# automotive-mirror-microcontroller-net-la.net
KiCad netlist of a schematic drawn in Altium Designer
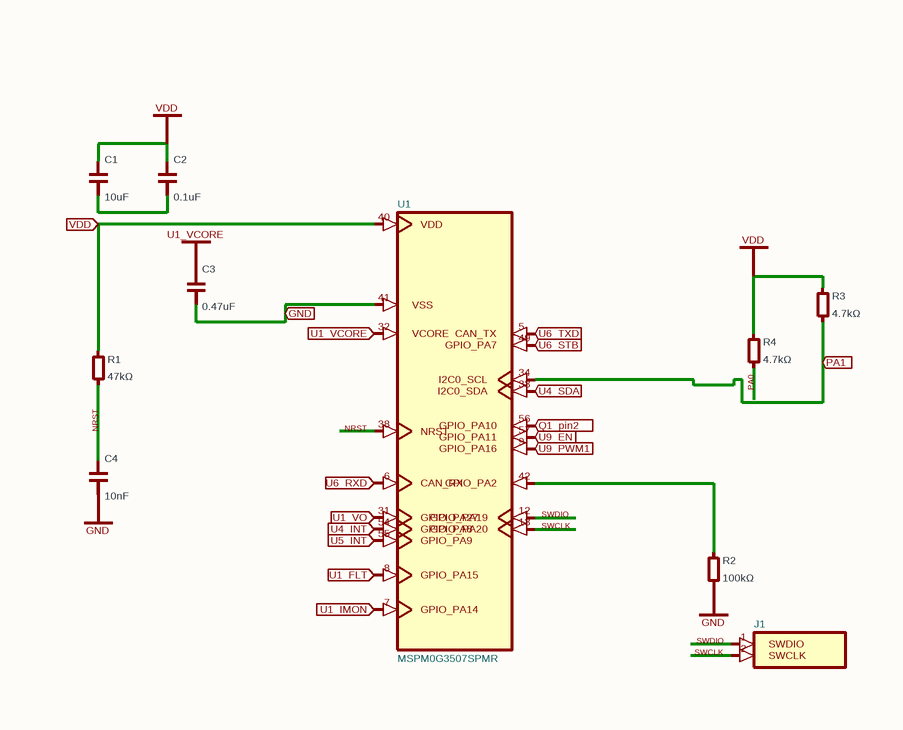
[diagram p0: automotive-mirror-microcontroller-net-label-text-4pt.SchDoc]

(export (version "E")
  (design (tool "Eeschema 10.0.6"))
  (components
    (comp (ref "C1") (value "10uF") (libsource (lib "altium-import") (part "root_0_capacitor_down_")))
    (comp (ref "C2") (value "0.1uF") (libsource (lib "altium-import") (part "root_0_capacitor_down_")))
    (comp (ref "C3") (value "0.47uF") (libsource (lib "altium-import") (part "root_0_capacitor_down_")))
    (comp (ref "C4") (value "10nF") (libsource (lib "altium-import") (part "root_0_capacitor_down_")))
    (comp (ref "J1") (value "~") (libsource (lib "altium-import") (part "root_0_J1_")))
    (comp (ref "R1") (value "47kΩ") (libsource (lib "altium-import") (part "root_0_boxresistor_up_")))
    (comp (ref "R2") (value "100kΩ") (libsource (lib "altium-import") (part "root_0_boxresistor_down_")))
    (comp (ref "R3") (value "4.7kΩ") (libsource (lib "altium-import") (part "root_0_boxresistor_up_")))
    (comp (ref "R4") (value "4.7kΩ") (libsource (lib "altium-import") (part "root_0_boxresistor_up_")))
    (comp (ref "U1") (value "~") (libsource (lib "altium-import") (part "root_0_U1_")))
  )
  (nets
    (net (code "1") (name "/PA1") (class "Default")
      (node (ref "R3") (pin "1") (pinfunction "anode_1") (pintype "input"))
      (node (ref "U1") (pin "34") (pinfunction "I2C0_SCL_34") (pintype "input"))
    )
    (net (code "2") (name "/Q1_pin2") (class "Default")
      (node (ref "U1") (pin "56") (pinfunction "GPIO_PA10_56") (pintype "input"))
    )
    (net (code "3") (name "/U1_FLT") (class "Default")
      (node (ref "U1") (pin "8") (pinfunction "GPIO_PA15_8") (pintype "input"))
    )
    (net (code "4") (name "/U1_IMON") (class "Default")
      (node (ref "U1") (pin "7") (pinfunction "GPIO_PA14_7") (pintype "input"))
    )
    (net (code "5") (name "/U1_VO") (class "Default")
      (node (ref "U1") (pin "31") (pinfunction "GPIO_PA27_31") (pintype "input"))
    )
    (net (code "6") (name "/U4_INT") (class "Default")
      (node (ref "U1") (pin "54") (pinfunction "GPIO_PA8_54") (pintype "input"))
    )
    (net (code "7") (name "/U4_SDA") (class "Default")
      (node (ref "U1") (pin "33") (pinfunction "I2C0_SDA_33") (pintype "input"))
    )
    (net (code "8") (name "/U5_INT") (class "Default")
      (node (ref "U1") (pin "55") (pinfunction "GPIO_PA9_55") (pintype "input"))
    )
    (net (code "9") (name "/U6_RXD") (class "Default")
      (node (ref "U1") (pin "6") (pinfunction "CAN_RX_6") (pintype "input"))
    )
    (net (code "10") (name "/U6_STB") (class "Default")
      (node (ref "U1") (pin "49") (pinfunction "GPIO_PA7_49") (pintype "input"))
    )
    (net (code "11") (name "/U6_TXD") (class "Default")
      (node (ref "U1") (pin "5") (pinfunction "CAN_TX_5") (pintype "input"))
    )
    (net (code "12") (name "/U9_EN") (class "Default")
      (node (ref "U1") (pin "57") (pinfunction "GPIO_PA11_57") (pintype "input"))
    )
    (net (code "13") (name "/U9_PWM1") (class "Default")
      (node (ref "U1") (pin "9") (pinfunction "GPIO_PA16_9") (pintype "input"))
    )
    (net (code "14") (name "GND") (class "Default")
      (node (ref "C3") (pin "2") (pinfunction "cathode_2") (pintype "input"))
      (node (ref "C4") (pin "2") (pinfunction "cathode_2") (pintype "input"))
      (node (ref "R2") (pin "2") (pinfunction "cathode_2") (pintype "input"))
      (node (ref "U1") (pin "41") (pinfunction "VSS_41") (pintype "input"))
    )
    (net (code "15") (name "Net-(C1-cathode)") (class "Default")
      (node (ref "C1") (pin "2") (pinfunction "cathode_2") (pintype "input"))
      (node (ref "C2") (pin "2") (pinfunction "cathode_2") (pintype "input"))
    )
    (net (code "16") (name "Net-(C4-anode)") (class "Default")
      (node (ref "C4") (pin "1") (pinfunction "anode_1") (pintype "input"))
      (node (ref "R1") (pin "1") (pinfunction "anode_1") (pintype "input"))
    )
    (net (code "17") (name "Net-(R2-anode)") (class "Default")
      (node (ref "R2") (pin "1") (pinfunction "anode_1") (pintype "input"))
      (node (ref "U1") (pin "42") (pinfunction "GPIO_PA2_42") (pintype "input"))
    )
    (net (code "18") (name "U1_VCORE") (class "Default")
      (node (ref "C3") (pin "1") (pinfunction "anode_1") (pintype "input"))
      (node (ref "U1") (pin "32") (pinfunction "VCORE_32") (pintype "input"))
    )
    (net (code "19") (name "VDD") (class "Default")
      (node (ref "C1") (pin "1") (pinfunction "anode_1") (pintype "input"))
      (node (ref "C2") (pin "1") (pinfunction "anode_1") (pintype "input"))
      (node (ref "R1") (pin "2") (pinfunction "cathode_2") (pintype "input"))
      (node (ref "R3") (pin "2") (pinfunction "cathode_2") (pintype "input"))
      (node (ref "R4") (pin "2") (pinfunction "cathode_2") (pintype "input"))
      (node (ref "U1") (pin "40") (pinfunction "VDD_40") (pintype "input"))
    )
    (net (code "20") (name "unconnected-(J1-SWCLK-Pad2)") (class "Default")
      (node (ref "J1") (pin "2") (pinfunction "SWCLK_2") (pintype "input"))
    )
    (net (code "21") (name "unconnected-(J1-SWDIO-Pad1)") (class "Default")
      (node (ref "J1") (pin "1") (pinfunction "SWDIO_1") (pintype "input"))
    )
    (net (code "22") (name "unconnected-(R4-anode-Pad1)") (class "Default")
      (node (ref "R4") (pin "1") (pinfunction "anode_1") (pintype "input"))
    )
    (net (code "23") (name "unconnected-(U1-GPIO_PA19-Pad12)") (class "Default")
      (node (ref "U1") (pin "12") (pinfunction "GPIO_PA19_12") (pintype "input"))
    )
    (net (code "24") (name "unconnected-(U1-GPIO_PA20-Pad13)") (class "Default")
      (node (ref "U1") (pin "13") (pinfunction "GPIO_PA20_13") (pintype "input"))
    )
    (net (code "25") (name "unconnected-(U1-NRST-Pad38)") (class "Default")
      (node (ref "U1") (pin "38") (pinfunction "NRST_38") (pintype "input"))
    )
  )
)
